# mainBoard.net
KiCad netlist of a schematic drawn in EAGLE
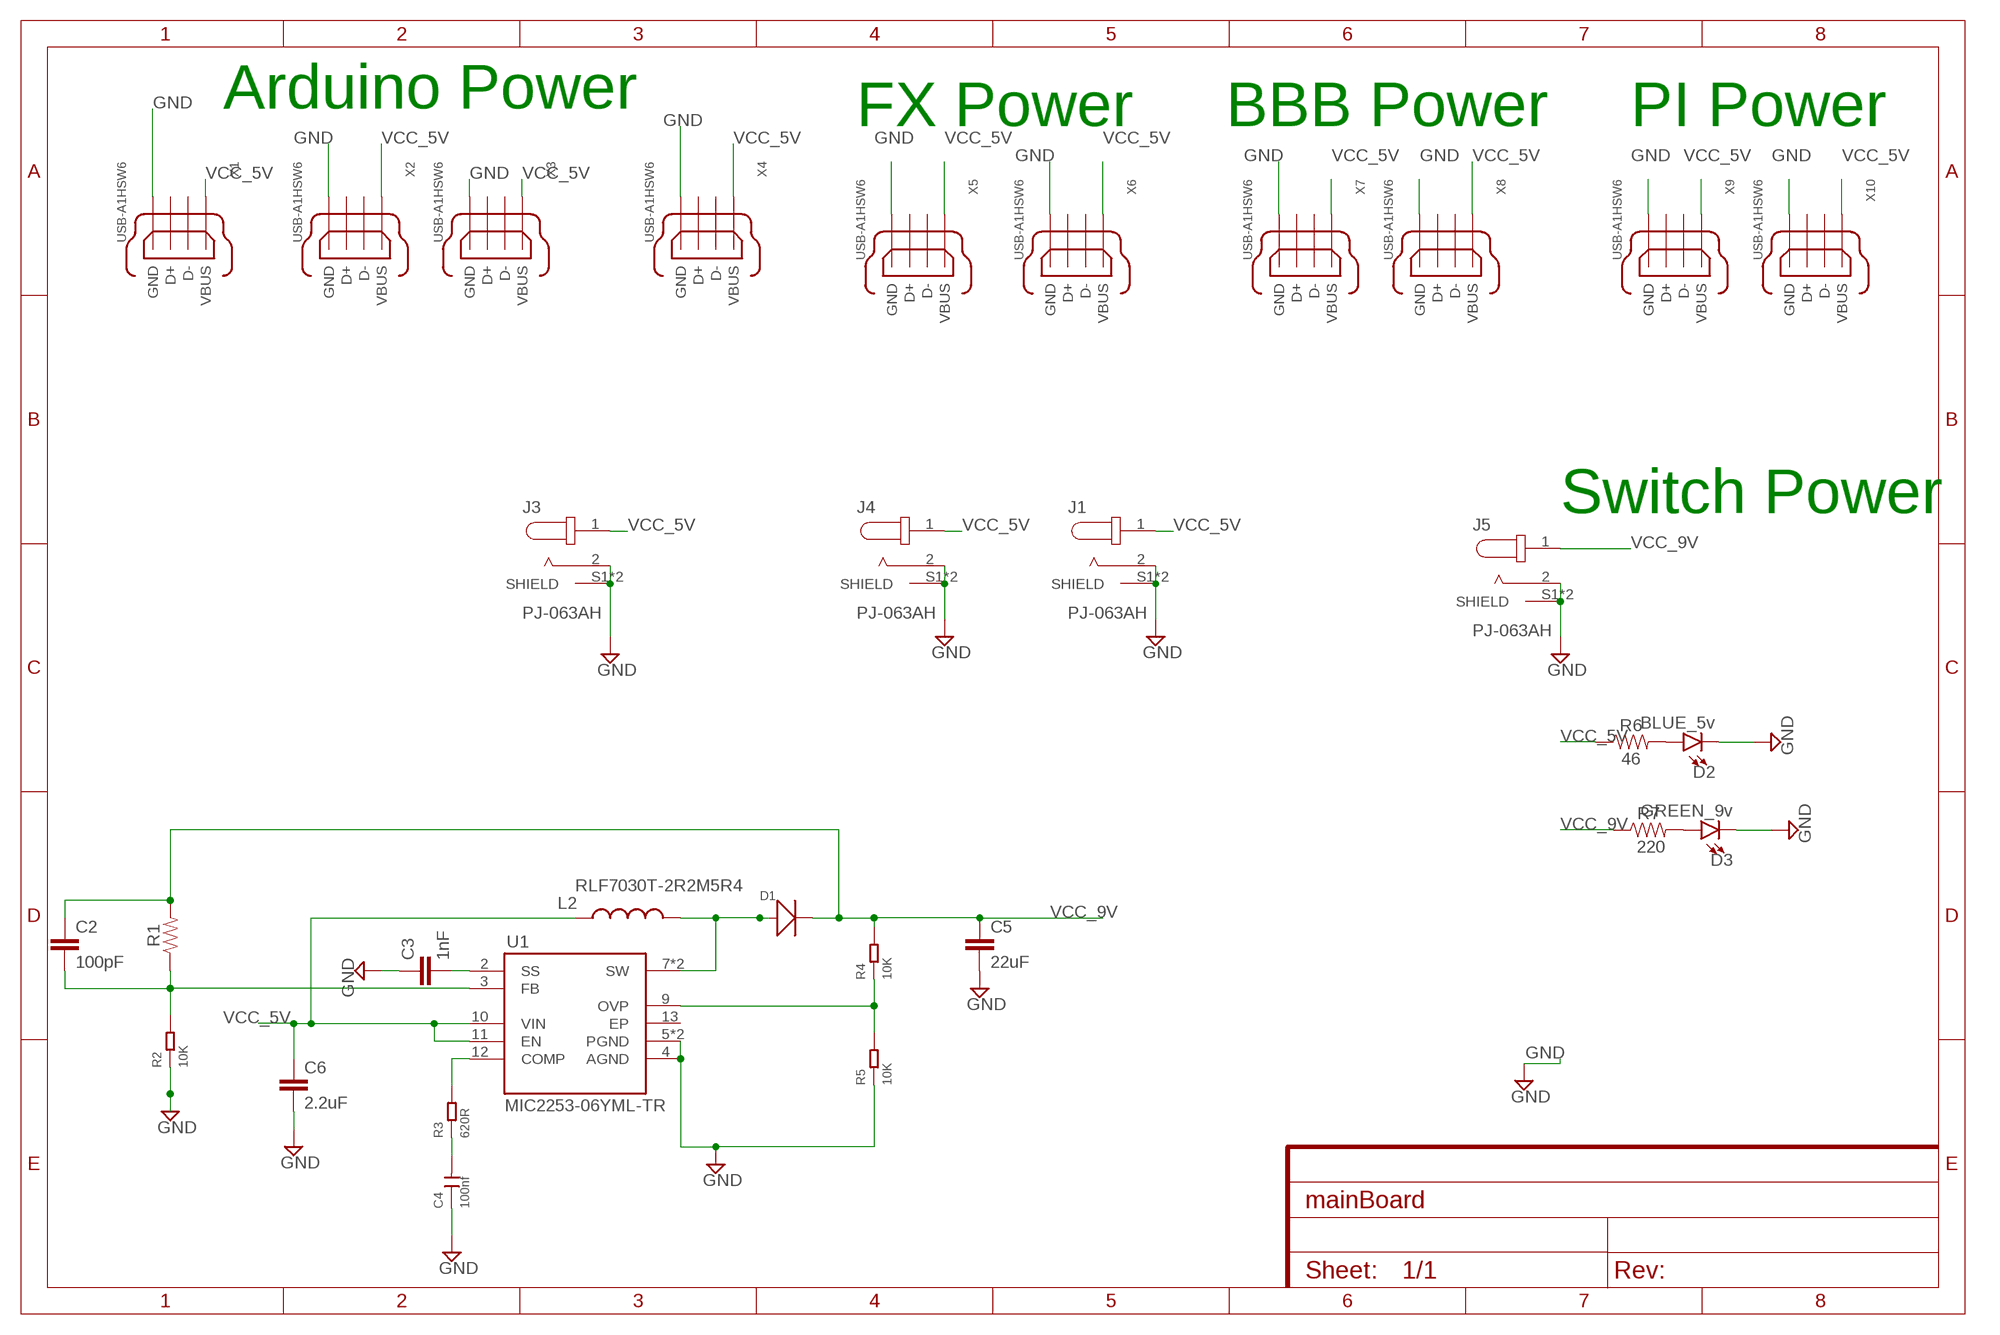
[diagram p0: schematic, sheet 1]

(export (version "E")
  (design (tool "Eeschema 10.0.6"))
  (components
    (comp (ref "C2")
      (value "100pF")
      (footprint "eagle-import:0603")
      (libsource (lib "eagle-import") (part "100PF-0603-50V-5%"))
    )
    (comp (ref "C3")
      (value "1nF")
      (footprint "eagle-import:0603")
      (libsource (lib "eagle-import") (part "1.0NF/1000PF-0603-50V-10%"))
    )
    (comp (ref "C4")
      (value "100nf")
      (footprint "eagle-import:C0402")
      (fields (field (name "MPN") "CC0402KRX7R8BB104"))
      (libsource (lib "eagle-import") (part "CERAMIC-100NF-25V-10%-X7R(0402)"))
    )
    (comp (ref "C5")
      (value "22uF")
      (footprint "eagle-import:0805")
      (libsource (lib "eagle-import") (part "22UF-0805-6.3V-20%"))
    )
    (comp (ref "C6")
      (value "2.2uF")
      (footprint "eagle-import:0603")
      (libsource (lib "eagle-import") (part "2.2UF-0603-10V-20%"))
    )
    (comp (ref "D1")
      (value "SMD-DIODE-SCHOTTKY-28V-5A(DO-214AA)")
      (footprint "eagle-import:DO-214AA")
      (fields (field (name "MPN") "SS54B"))
      (libsource (lib "eagle-import") (part "SMD-DIODE-SCHOTTKY-28V-5A(DO-214AA)"))
    )
    (comp (ref "D2")
      (value "BLUE_5v")
      (footprint "eagle-import:LED-0603")
      (libsource (lib "eagle-import") (part "LED-BLUE0603"))
    )
    (comp (ref "D3")
      (value "GREEN_9v")
      (footprint "eagle-import:LED-0603")
      (libsource (lib "eagle-import") (part "LED-GREEN0603"))
    )
    (comp (ref "J1")
      (value "PJ-063AH")
      (footprint "eagle-import:CUI_PJ-063AH")
      (fields (field (name "MF") "CUI Inc."))
      (libsource (lib "eagle-import") (part "PJ-063AH"))
    )
    (comp (ref "J3")
      (value "PJ-063AH")
      (footprint "eagle-import:CUI_PJ-063AH")
      (fields (field (name "MF") "CUI Inc."))
      (libsource (lib "eagle-import") (part "PJ-063AH"))
    )
    (comp (ref "J4")
      (value "PJ-063AH")
      (footprint "eagle-import:CUI_PJ-063AH")
      (fields (field (name "MF") "CUI Inc."))
      (libsource (lib "eagle-import") (part "PJ-063AH"))
    )
    (comp (ref "J5")
      (value "PJ-063AH")
      (footprint "eagle-import:CUI_PJ-063AH")
      (fields (field (name "MF") "CUI Inc."))
      (libsource (lib "eagle-import") (part "PJ-063AH"))
    )
    (comp (ref "L2")
      (value "RLF7030T-2R2M5R4")
      (footprint "eagle-import:INDP7368X320")
      (fields (field (name "MF") "TDK"))
      (libsource (lib "eagle-import") (part "RLF7030T-2R2M5R4"))
    )
    (comp (ref "R1")
      (value "62KOHM-0603-1/10W-5%")
      (footprint "eagle-import:0603")
      (libsource (lib "eagle-import") (part "62KOHM-0603-1/10W-5%"))
    )
    (comp (ref "R2")
      (value "10K")
      (footprint "eagle-import:R0603")
      (fields (field (name "MPN") "RC0603FR-0710KL"))
      (libsource (lib "eagle-import") (part "SMD-RES-10K-1%-1/10W(0603)"))
    )
    (comp (ref "R3")
      (value "620R")
      (footprint "eagle-import:R0603")
      (fields (field (name "MPN") "RC0603JR-07620RL"))
      (libsource (lib "eagle-import") (part "SMD-RES-620R-5%-1/10W(0603)"))
    )
    (comp (ref "R4")
      (value "10K")
      (footprint "eagle-import:R0603")
      (fields (field (name "MPN") "RC0603FR-0710KL"))
      (libsource (lib "eagle-import") (part "SMD-RES-10K-1%-1/10W(0603)"))
    )
    (comp (ref "R5")
      (value "10K")
      (footprint "eagle-import:R0603")
      (fields (field (name "MPN") "RC0603FR-0710KL"))
      (libsource (lib "eagle-import") (part "SMD-RES-10K-1%-1/10W(0603)"))
    )
    (comp (ref "R6")
      (value "46")
      (footprint "eagle-import:0603")
      (libsource (lib "eagle-import") (part "RESISTOR0603"))
    )
    (comp (ref "R7")
      (value "220")
      (footprint "eagle-import:0603")
      (libsource (lib "eagle-import") (part "RESISTOR0603"))
    )
    (comp (ref "U1")
      (value "MIC2253-06YML-TR")
      (footprint "eagle-import:SON50P300X300X90-13N")
      (fields (field (name "DIGI-KEY_PART_NUMBER") "576-3643-1-ND") (field (name "MF") "Microchip"))
      (libsource (lib "eagle-import") (part "MIC2253-06YML-TR"))
    )
    (comp (ref "X1")
      (value "USB-A1HSW6")
      (footprint "eagle-import:OST_USB-A1HSW6")
      (fields (field (name "MF") "On Shore"))
      (libsource (lib "eagle-import") (part "USB-A1HSW6"))
    )
    (comp (ref "X2")
      (value "USB-A1HSW6")
      (footprint "eagle-import:OST_USB-A1HSW6")
      (fields (field (name "MF") "On Shore"))
      (libsource (lib "eagle-import") (part "USB-A1HSW6"))
    )
    (comp (ref "X3")
      (value "USB-A1HSW6")
      (footprint "eagle-import:OST_USB-A1HSW6")
      (fields (field (name "MF") "On Shore"))
      (libsource (lib "eagle-import") (part "USB-A1HSW6"))
    )
    (comp (ref "X4")
      (value "USB-A1HSW6")
      (footprint "eagle-import:OST_USB-A1HSW6")
      (fields (field (name "MF") "On Shore"))
      (libsource (lib "eagle-import") (part "USB-A1HSW6"))
    )
    (comp (ref "X5")
      (value "USB-A1HSW6")
      (footprint "eagle-import:OST_USB-A1HSW6")
      (fields (field (name "MF") "On Shore"))
      (libsource (lib "eagle-import") (part "USB-A1HSW6"))
    )
    (comp (ref "X6")
      (value "USB-A1HSW6")
      (footprint "eagle-import:OST_USB-A1HSW6")
      (fields (field (name "MF") "On Shore"))
      (libsource (lib "eagle-import") (part "USB-A1HSW6"))
    )
    (comp (ref "X7")
      (value "USB-A1HSW6")
      (footprint "eagle-import:OST_USB-A1HSW6")
      (fields (field (name "MF") "On Shore"))
      (libsource (lib "eagle-import") (part "USB-A1HSW6"))
    )
    (comp (ref "X8")
      (value "USB-A1HSW6")
      (footprint "eagle-import:OST_USB-A1HSW6")
      (fields (field (name "MF") "On Shore"))
      (libsource (lib "eagle-import") (part "USB-A1HSW6"))
    )
    (comp (ref "X9")
      (value "USB-A1HSW6")
      (footprint "eagle-import:OST_USB-A1HSW6")
      (fields (field (name "MF") "On Shore"))
      (libsource (lib "eagle-import") (part "USB-A1HSW6"))
    )
    (comp (ref "X10")
      (value "USB-A1HSW6")
      (footprint "eagle-import:OST_USB-A1HSW6")
      (fields (field (name "MF") "On Shore"))
      (libsource (lib "eagle-import") (part "USB-A1HSW6"))
    )
  )
  (nets
    (net (code "1") (name "/VCC_5V") (class "Default")
      (node (ref "C6") (pin "1") (pinfunction "1_1") (pintype "passive"))
      (node (ref "J1") (pin "1") (pinfunction "1_1") (pintype "passive"))
      (node (ref "J3") (pin "1") (pinfunction "1_1") (pintype "passive"))
      (node (ref "J4") (pin "1") (pinfunction "1_1") (pintype "passive"))
      (node (ref "L2") (pin "1") (pinfunction "1_1") (pintype "passive"))
      (node (ref "R6") (pin "1") (pinfunction "1_1") (pintype "passive"))
      (node (ref "U1") (pin "10") (pinfunction "VIN_10") (pintype "input"))
      (node (ref "U1") (pin "11") (pinfunction "EN_11") (pintype "input"))
      (node (ref "X1") (pin "1") (pinfunction "VBUS_1") (pintype "power_in"))
      (node (ref "X10") (pin "1") (pinfunction "VBUS_1") (pintype "power_in"))
      (node (ref "X2") (pin "1") (pinfunction "VBUS_1") (pintype "power_in"))
      (node (ref "X3") (pin "1") (pinfunction "VBUS_1") (pintype "power_in"))
      (node (ref "X4") (pin "1") (pinfunction "VBUS_1") (pintype "power_in"))
      (node (ref "X5") (pin "1") (pinfunction "VBUS_1") (pintype "power_in"))
      (node (ref "X6") (pin "1") (pinfunction "VBUS_1") (pintype "power_in"))
      (node (ref "X7") (pin "1") (pinfunction "VBUS_1") (pintype "power_in"))
      (node (ref "X8") (pin "1") (pinfunction "VBUS_1") (pintype "power_in"))
      (node (ref "X9") (pin "1") (pinfunction "VBUS_1") (pintype "power_in"))
    )
    (net (code "2") (name "/VCC_9V") (class "Default")
      (node (ref "C2") (pin "1") (pinfunction "1_1") (pintype "passive"))
      (node (ref "C5") (pin "1") (pinfunction "1_1") (pintype "passive"))
      (node (ref "D1") (pin "-") (pinfunction "-_-") (pintype "passive"))
      (node (ref "J5") (pin "1") (pinfunction "1_1") (pintype "passive"))
      (node (ref "R1") (pin "2") (pinfunction "2_2") (pintype "passive"))
      (node (ref "R4") (pin "2") (pinfunction "2_2") (pintype "passive"))
      (node (ref "R7") (pin "1") (pinfunction "1_1") (pintype "passive"))
    )
    (net (code "3") (name "GND") (class "Default")
      (node (ref "C3") (pin "1") (pinfunction "1_1") (pintype "passive"))
      (node (ref "C4") (pin "1") (pinfunction "1_1") (pintype "passive"))
      (node (ref "C5") (pin "2") (pinfunction "2_2") (pintype "passive"))
      (node (ref "C6") (pin "2") (pinfunction "2_2") (pintype "passive"))
      (node (ref "D2") (pin "C") (pinfunction "C_C") (pintype "passive"))
      (node (ref "D3") (pin "C") (pinfunction "C_C") (pintype "passive"))
      (node (ref "J1") (pin "2") (pinfunction "2_2") (pintype "passive"))
      (node (ref "J1") (pin "S1") (pinfunction "SHIELD_S1") (pintype "power_in"))
      (node (ref "J1") (pin "S2") (pinfunction "SHIELD_S2") (pintype "power_in"))
      (node (ref "J3") (pin "2") (pinfunction "2_2") (pintype "passive"))
      (node (ref "J3") (pin "S1") (pinfunction "SHIELD_S1") (pintype "power_in"))
      (node (ref "J3") (pin "S2") (pinfunction "SHIELD_S2") (pintype "power_in"))
      (node (ref "J4") (pin "2") (pinfunction "2_2") (pintype "passive"))
      (node (ref "J4") (pin "S1") (pinfunction "SHIELD_S1") (pintype "power_in"))
      (node (ref "J4") (pin "S2") (pinfunction "SHIELD_S2") (pintype "power_in"))
      (node (ref "J5") (pin "2") (pinfunction "2_2") (pintype "passive"))
      (node (ref "J5") (pin "S1") (pinfunction "SHIELD_S1") (pintype "power_in"))
      (node (ref "J5") (pin "S2") (pinfunction "SHIELD_S2") (pintype "power_in"))
      (node (ref "R2") (pin "1") (pinfunction "1_1") (pintype "passive"))
      (node (ref "R5") (pin "1") (pinfunction "1_1") (pintype "passive"))
      (node (ref "U1") (pin "4") (pinfunction "AGND_4") (pintype "power_in"))
      (node (ref "U1") (pin "5") (pinfunction "PGND_5") (pintype "power_in"))
      (node (ref "U1") (pin "6") (pinfunction "PGND_6") (pintype "power_in"))
      (node (ref "X1") (pin "4") (pinfunction "GND_4") (pintype "power_in"))
      (node (ref "X10") (pin "4") (pinfunction "GND_4") (pintype "power_in"))
      (node (ref "X2") (pin "4") (pinfunction "GND_4") (pintype "power_in"))
      (node (ref "X3") (pin "4") (pinfunction "GND_4") (pintype "power_in"))
      (node (ref "X4") (pin "4") (pinfunction "GND_4") (pintype "power_in"))
      (node (ref "X5") (pin "4") (pinfunction "GND_4") (pintype "power_in"))
      (node (ref "X6") (pin "4") (pinfunction "GND_4") (pintype "power_in"))
      (node (ref "X7") (pin "4") (pinfunction "GND_4") (pintype "power_in"))
      (node (ref "X8") (pin "4") (pinfunction "GND_4") (pintype "power_in"))
      (node (ref "X9") (pin "4") (pinfunction "GND_4") (pintype "power_in"))
    )
    (net (code "4") (name "Net-(C4-Pad2)") (class "Default")
      (node (ref "C4") (pin "2") (pinfunction "2_2") (pintype "passive"))
      (node (ref "R3") (pin "1") (pinfunction "1_1") (pintype "passive"))
    )
    (net (code "5") (name "Net-(D1-Pad+)") (class "Default")
      (node (ref "D1") (pin "+") (pinfunction "+_+") (pintype "passive"))
      (node (ref "L2") (pin "2") (pinfunction "2_2") (pintype "passive"))
      (node (ref "U1") (pin "7") (pinfunction "SW_7") (pintype "bidirectional"))
      (node (ref "U1") (pin "8") (pinfunction "SW_8") (pintype "bidirectional"))
    )
    (net (code "6") (name "Net-(D2-PadA)") (class "Default")
      (node (ref "D2") (pin "A") (pinfunction "A_A") (pintype "passive"))
      (node (ref "R6") (pin "2") (pinfunction "2_2") (pintype "passive"))
    )
    (net (code "7") (name "Net-(D3-PadA)") (class "Default")
      (node (ref "D3") (pin "A") (pinfunction "A_A") (pintype "passive"))
      (node (ref "R7") (pin "2") (pinfunction "2_2") (pintype "passive"))
    )
    (net (code "8") (name "Net-(U1-COMP)") (class "Default")
      (node (ref "R3") (pin "2") (pinfunction "2_2") (pintype "passive"))
      (node (ref "U1") (pin "12") (pinfunction "COMP_12") (pintype "input"))
    )
    (net (code "9") (name "Net-(U1-FB)") (class "Default")
      (node (ref "C2") (pin "2") (pinfunction "2_2") (pintype "passive"))
      (node (ref "R1") (pin "1") (pinfunction "1_1") (pintype "passive"))
      (node (ref "R2") (pin "2") (pinfunction "2_2") (pintype "passive"))
      (node (ref "U1") (pin "3") (pinfunction "FB_3") (pintype "input"))
    )
    (net (code "10") (name "Net-(U1-OVP)") (class "Default")
      (node (ref "R4") (pin "1") (pinfunction "1_1") (pintype "passive"))
      (node (ref "R5") (pin "2") (pinfunction "2_2") (pintype "passive"))
      (node (ref "U1") (pin "9") (pinfunction "OVP_9") (pintype "passive"))
    )
    (net (code "11") (name "Net-(U1-SS)") (class "Default")
      (node (ref "C3") (pin "2") (pinfunction "2_2") (pintype "passive"))
      (node (ref "U1") (pin "2") (pinfunction "SS_2") (pintype "input"))
    )
    (net (code "12") (name "unconnected-(U1-EP-Pad13)") (class "Default")
      (node (ref "U1") (pin "13") (pinfunction "EP_13") (pintype "passive"))
    )
    (net (code "13") (name "unconnected-(X1-D+-Pad3)") (class "Default")
      (node (ref "X1") (pin "3") (pinfunction "D+_3") (pintype "bidirectional"))
    )
    (net (code "14") (name "unconnected-(X1-D--Pad2)") (class "Default")
      (node (ref "X1") (pin "2") (pinfunction "D-_2") (pintype "bidirectional"))
    )
    (net (code "15") (name "unconnected-(X2-D+-Pad3)") (class "Default")
      (node (ref "X2") (pin "3") (pinfunction "D+_3") (pintype "bidirectional"))
    )
    (net (code "16") (name "unconnected-(X2-D--Pad2)") (class "Default")
      (node (ref "X2") (pin "2") (pinfunction "D-_2") (pintype "bidirectional"))
    )
    (net (code "17") (name "unconnected-(X3-D+-Pad3)") (class "Default")
      (node (ref "X3") (pin "3") (pinfunction "D+_3") (pintype "bidirectional"))
    )
    (net (code "18") (name "unconnected-(X3-D--Pad2)") (class "Default")
      (node (ref "X3") (pin "2") (pinfunction "D-_2") (pintype "bidirectional"))
    )
    (net (code "19") (name "unconnected-(X4-D+-Pad3)") (class "Default")
      (node (ref "X4") (pin "3") (pinfunction "D+_3") (pintype "bidirectional"))
    )
    (net (code "20") (name "unconnected-(X4-D--Pad2)") (class "Default")
      (node (ref "X4") (pin "2") (pinfunction "D-_2") (pintype "bidirectional"))
    )
    (net (code "21") (name "unconnected-(X5-D+-Pad3)") (class "Default")
      (node (ref "X5") (pin "3") (pinfunction "D+_3") (pintype "bidirectional"))
    )
    (net (code "22") (name "unconnected-(X5-D--Pad2)") (class "Default")
      (node (ref "X5") (pin "2") (pinfunction "D-_2") (pintype "bidirectional"))
    )
    (net (code "23") (name "unconnected-(X6-D+-Pad3)") (class "Default")
      (node (ref "X6") (pin "3") (pinfunction "D+_3") (pintype "bidirectional"))
    )
    (net (code "24") (name "unconnected-(X6-D--Pad2)") (class "Default")
      (node (ref "X6") (pin "2") (pinfunction "D-_2") (pintype "bidirectional"))
    )
    (net (code "25") (name "unconnected-(X7-D+-Pad3)") (class "Default")
      (node (ref "X7") (pin "3") (pinfunction "D+_3") (pintype "bidirectional"))
    )
    (net (code "26") (name "unconnected-(X7-D--Pad2)") (class "Default")
      (node (ref "X7") (pin "2") (pinfunction "D-_2") (pintype "bidirectional"))
    )
    (net (code "27") (name "unconnected-(X8-D+-Pad3)") (class "Default")
      (node (ref "X8") (pin "3") (pinfunction "D+_3") (pintype "bidirectional"))
    )
    (net (code "28") (name "unconnected-(X8-D--Pad2)") (class "Default")
      (node (ref "X8") (pin "2") (pinfunction "D-_2") (pintype "bidirectional"))
    )
    (net (code "29") (name "unconnected-(X9-D+-Pad3)") (class "Default")
      (node (ref "X9") (pin "3") (pinfunction "D+_3") (pintype "bidirectional"))
    )
    (net (code "30") (name "unconnected-(X9-D--Pad2)") (class "Default")
      (node (ref "X9") (pin "2") (pinfunction "D-_2") (pintype "bidirectional"))
    )
    (net (code "31") (name "unconnected-(X10-D+-Pad3)") (class "Default")
      (node (ref "X10") (pin "3") (pinfunction "D+_3") (pintype "bidirectional"))
    )
    (net (code "32") (name "unconnected-(X10-D--Pad2)") (class "Default")
      (node (ref "X10") (pin "2") (pinfunction "D-_2") (pintype "bidirectional"))
    )
  )
)
